# HDMI_INPUT_AD9398.net
KiCad netlist of a schematic drawn in Altium Designer
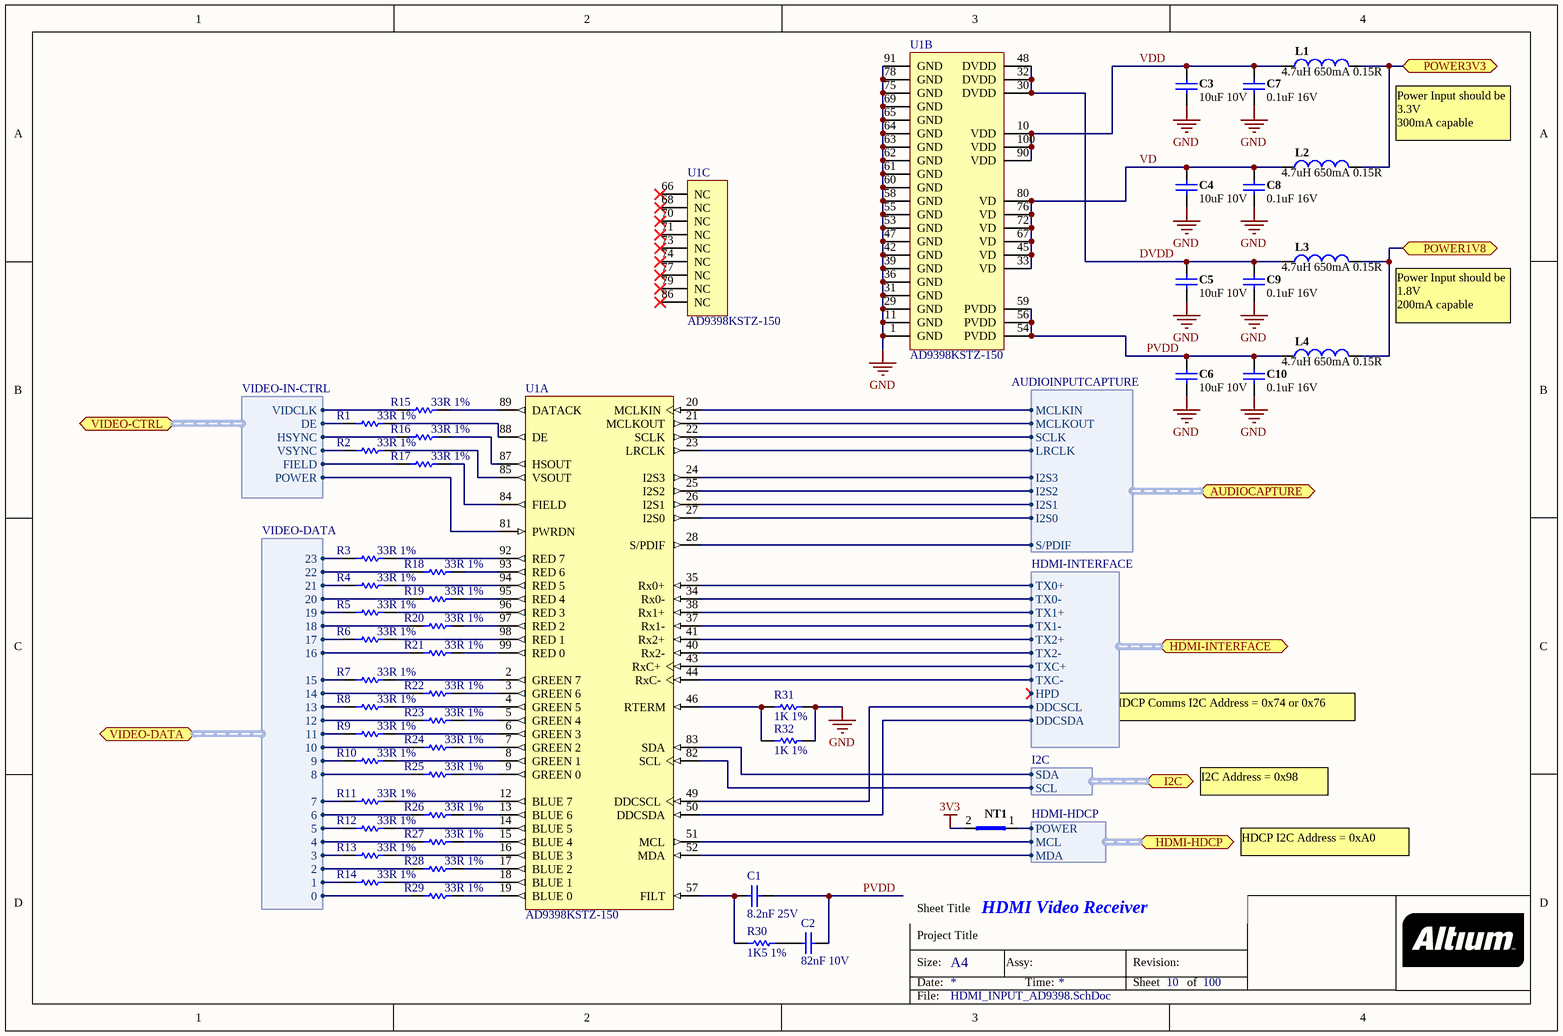
[diagram p0: HDMI_INPUT_AD9398.SchDoc]

(export (version "E")
  (design (tool "Eeschema 10.0.6"))
  (components
    (comp (ref "C1")
      (value "8.2nF 25V")
      (footprint "CAPC1005-STAR")
      (description "Capacitor, Ceramic, 8.2nF, X7R, 25V, 10%, 0402")
      (fields (field (name "TOLERANCE") "10 %"))
      (libsource (lib "AltiumDesignLibrary") (part "CAP-NP"))
    )
    (comp (ref "C2")
      (value "82nF 10V")
      (footprint "CAPC1005-STAR")
      (description "Capacitor, Ceramic, 82nF, X5R, 10V, 10%, 0402")
      (fields (field (name "TOLERANCE") "10 %"))
      (libsource (lib "AltiumDesignLibrary") (part "CAP-NP"))
    )
    (comp (ref "C3")
      (value "10uF 10V")
      (footprint "CAPC2012-STAR")
      (description "Capacitor, Ceramic, 10uF 10% 10V 0805 (2012) X5R")
      (fields (field (name "TOLERANCE") "10 %"))
      (libsource (lib "AltiumDesignLibrary") (part "CAP-NP"))
    )
    (comp (ref "C4")
      (value "10uF 10V")
      (footprint "CAPC2012-STAR")
      (description "Capacitor, Ceramic, 10uF 10% 10V 0805 (2012) X5R")
      (fields (field (name "TOLERANCE") "10 %"))
      (libsource (lib "AltiumDesignLibrary") (part "CAP-NP"))
    )
    (comp (ref "C5")
      (value "10uF 10V")
      (footprint "CAPC2012-STAR")
      (description "Capacitor, Ceramic, 10uF 10% 10V 0805 (2012) X5R")
      (fields (field (name "TOLERANCE") "10 %"))
      (libsource (lib "AltiumDesignLibrary") (part "CAP-NP"))
    )
    (comp (ref "C6")
      (value "10uF 10V")
      (footprint "CAPC2012-STAR")
      (description "Capacitor, Ceramic, 10uF 10% 10V 0805 (2012) X5R")
      (fields (field (name "TOLERANCE") "10 %"))
      (libsource (lib "AltiumDesignLibrary") (part "CAP-NP"))
    )
    (comp (ref "C7")
      (value "0.1uF 16V")
      (footprint "CAPC1005-STAR")
      (description "Capacitor, Ceramic, 0.1uF 10% 16V 0402 (1005) X7R")
      (fields (field (name "TOLERANCE") "10 %"))
      (libsource (lib "AltiumDesignLibrary") (part "CAP-NP"))
    )
    (comp (ref "C8")
      (value "0.1uF 16V")
      (footprint "CAPC1005-STAR")
      (description "Capacitor, Ceramic, 0.1uF 10% 16V 0402 (1005) X7R")
      (fields (field (name "TOLERANCE") "10 %"))
      (libsource (lib "AltiumDesignLibrary") (part "CAP-NP"))
    )
    (comp (ref "C9")
      (value "0.1uF 16V")
      (footprint "CAPC1005-STAR")
      (description "Capacitor, Ceramic, 0.1uF 10% 16V 0402 (1005) X7R")
      (fields (field (name "TOLERANCE") "10 %"))
      (libsource (lib "AltiumDesignLibrary") (part "CAP-NP"))
    )
    (comp (ref "C10")
      (value "0.1uF 16V")
      (footprint "CAPC1005-STAR")
      (description "Capacitor, Ceramic, 0.1uF 10% 16V 0402 (1005) X7R")
      (fields (field (name "TOLERANCE") "10 %"))
      (libsource (lib "AltiumDesignLibrary") (part "CAP-NP"))
    )
    (comp (ref "L1")
      (value "4.7uH 650mA 0.15R")
      (footprint "INDC3225")
      (description "Inductor, 4.7uH 650mA 0.15R 1210 (3225) LQH32CN4R7M11L")
      (libsource (lib "AltiumDesignLibrary") (part "IND"))
    )
    (comp (ref "L2")
      (value "4.7uH 650mA 0.15R")
      (footprint "INDC3225")
      (description "Inductor, 4.7uH 650mA 0.15R 1210 (3225) LQH32CN4R7M11L")
      (libsource (lib "AltiumDesignLibrary") (part "IND"))
    )
    (comp (ref "L3")
      (value "4.7uH 650mA 0.15R")
      (footprint "INDC3225")
      (description "Inductor, 4.7uH 650mA 0.15R 1210 (3225) LQH32CN4R7M11L")
      (libsource (lib "AltiumDesignLibrary") (part "IND"))
    )
    (comp (ref "L4")
      (value "4.7uH 650mA 0.15R")
      (footprint "INDC3225")
      (description "Inductor, 4.7uH 650mA 0.15R 1210 (3225) LQH32CN4R7M11L")
      (libsource (lib "AltiumDesignLibrary") (part "IND"))
    )
    (comp (ref "NT1")
      (value "Net Tie SMT2")
      (footprint "NETTIE-SMT2-31X39")
      (description "Net-Tie, Surface Mount, 2 x 2.0mm x 0.8mm SMT Pads - For 0.8mm Track")
      (libsource (lib "AltiumDesignLibrary") (part "NETTIE-SMT2"))
    )
    (comp (ref "R1")
      (value "33R 1%")
      (footprint "RESC1005-STAR")
      (description "Resistor, 33R 1% 0402 (1005)")
      (fields (field (name "TOLERANCE") "1 %"))
      (libsource (lib "AltiumDesignLibrary") (part "RES"))
    )
    (comp (ref "R2")
      (value "33R 1%")
      (footprint "RESC1005-STAR")
      (description "Resistor, 33R 1% 0402 (1005)")
      (fields (field (name "TOLERANCE") "1 %"))
      (libsource (lib "AltiumDesignLibrary") (part "RES"))
    )
    (comp (ref "R3")
      (value "33R 1%")
      (footprint "RESC1005-STAR")
      (description "Resistor, 33R 1% 0402 (1005)")
      (fields (field (name "TOLERANCE") "1 %"))
      (libsource (lib "AltiumDesignLibrary") (part "RES"))
    )
    (comp (ref "R4")
      (value "33R 1%")
      (footprint "RESC1005-STAR")
      (description "Resistor, 33R 1% 0402 (1005)")
      (fields (field (name "TOLERANCE") "1 %"))
      (libsource (lib "AltiumDesignLibrary") (part "RES"))
    )
    (comp (ref "R5")
      (value "33R 1%")
      (footprint "RESC1005-STAR")
      (description "Resistor, 33R 1% 0402 (1005)")
      (fields (field (name "TOLERANCE") "1 %"))
      (libsource (lib "AltiumDesignLibrary") (part "RES"))
    )
    (comp (ref "R6")
      (value "33R 1%")
      (footprint "RESC1005-STAR")
      (description "Resistor, 33R 1% 0402 (1005)")
      (fields (field (name "TOLERANCE") "1 %"))
      (libsource (lib "AltiumDesignLibrary") (part "RES"))
    )
    (comp (ref "R7")
      (value "33R 1%")
      (footprint "RESC1005-STAR")
      (description "Resistor, 33R 1% 0402 (1005)")
      (fields (field (name "TOLERANCE") "1 %"))
      (libsource (lib "AltiumDesignLibrary") (part "RES"))
    )
    (comp (ref "R8")
      (value "33R 1%")
      (footprint "RESC1005-STAR")
      (description "Resistor, 33R 1% 0402 (1005)")
      (fields (field (name "TOLERANCE") "1 %"))
      (libsource (lib "AltiumDesignLibrary") (part "RES"))
    )
    (comp (ref "R9")
      (value "33R 1%")
      (footprint "RESC1005-STAR")
      (description "Resistor, 33R 1% 0402 (1005)")
      (fields (field (name "TOLERANCE") "1 %"))
      (libsource (lib "AltiumDesignLibrary") (part "RES"))
    )
    (comp (ref "R10")
      (value "33R 1%")
      (footprint "RESC1005-STAR")
      (description "Resistor, 33R 1% 0402 (1005)")
      (fields (field (name "TOLERANCE") "1 %"))
      (libsource (lib "AltiumDesignLibrary") (part "RES"))
    )
    (comp (ref "R11")
      (value "33R 1%")
      (footprint "RESC1005-STAR")
      (description "Resistor, 33R 1% 0402 (1005)")
      (fields (field (name "TOLERANCE") "1 %"))
      (libsource (lib "AltiumDesignLibrary") (part "RES"))
    )
    (comp (ref "R12")
      (value "33R 1%")
      (footprint "RESC1005-STAR")
      (description "Resistor, 33R 1% 0402 (1005)")
      (fields (field (name "TOLERANCE") "1 %"))
      (libsource (lib "AltiumDesignLibrary") (part "RES"))
    )
    (comp (ref "R13")
      (value "33R 1%")
      (footprint "RESC1005-STAR")
      (description "Resistor, 33R 1% 0402 (1005)")
      (fields (field (name "TOLERANCE") "1 %"))
      (libsource (lib "AltiumDesignLibrary") (part "RES"))
    )
    (comp (ref "R14")
      (value "33R 1%")
      (footprint "RESC1005-STAR")
      (description "Resistor, 33R 1% 0402 (1005)")
      (fields (field (name "TOLERANCE") "1 %"))
      (libsource (lib "AltiumDesignLibrary") (part "RES"))
    )
    (comp (ref "R15")
      (value "33R 1%")
      (footprint "RESC1005-STAR")
      (description "Resistor, 33R 1% 0402 (1005)")
      (fields (field (name "TOLERANCE") "1 %"))
      (libsource (lib "AltiumDesignLibrary") (part "RES"))
    )
    (comp (ref "R16")
      (value "33R 1%")
      (footprint "RESC1005-STAR")
      (description "Resistor, 33R 1% 0402 (1005)")
      (fields (field (name "TOLERANCE") "1 %"))
      (libsource (lib "AltiumDesignLibrary") (part "RES"))
    )
    (comp (ref "R17")
      (value "33R 1%")
      (footprint "RESC1005-STAR")
      (description "Resistor, 33R 1% 0402 (1005)")
      (fields (field (name "TOLERANCE") "1 %"))
      (libsource (lib "AltiumDesignLibrary") (part "RES"))
    )
    (comp (ref "R18")
      (value "33R 1%")
      (footprint "RESC1005-STAR")
      (description "Resistor, 33R 1% 0402 (1005)")
      (fields (field (name "TOLERANCE") "1 %"))
      (libsource (lib "AltiumDesignLibrary") (part "RES"))
    )
    (comp (ref "R19")
      (value "33R 1%")
      (footprint "RESC1005-STAR")
      (description "Resistor, 33R 1% 0402 (1005)")
      (fields (field (name "TOLERANCE") "1 %"))
      (libsource (lib "AltiumDesignLibrary") (part "RES"))
    )
    (comp (ref "R20")
      (value "33R 1%")
      (footprint "RESC1005-STAR")
      (description "Resistor, 33R 1% 0402 (1005)")
      (fields (field (name "TOLERANCE") "1 %"))
      (libsource (lib "AltiumDesignLibrary") (part "RES"))
    )
    (comp (ref "R21")
      (value "33R 1%")
      (footprint "RESC1005-STAR")
      (description "Resistor, 33R 1% 0402 (1005)")
      (fields (field (name "TOLERANCE") "1 %"))
      (libsource (lib "AltiumDesignLibrary") (part "RES"))
    )
    (comp (ref "R22")
      (value "33R 1%")
      (footprint "RESC1005-STAR")
      (description "Resistor, 33R 1% 0402 (1005)")
      (fields (field (name "TOLERANCE") "1 %"))
      (libsource (lib "AltiumDesignLibrary") (part "RES"))
    )
    (comp (ref "R23")
      (value "33R 1%")
      (footprint "RESC1005-STAR")
      (description "Resistor, 33R 1% 0402 (1005)")
      (fields (field (name "TOLERANCE") "1 %"))
      (libsource (lib "AltiumDesignLibrary") (part "RES"))
    )
    (comp (ref "R24")
      (value "33R 1%")
      (footprint "RESC1005-STAR")
      (description "Resistor, 33R 1% 0402 (1005)")
      (fields (field (name "TOLERANCE") "1 %"))
      (libsource (lib "AltiumDesignLibrary") (part "RES"))
    )
    (comp (ref "R25")
      (value "33R 1%")
      (footprint "RESC1005-STAR")
      (description "Resistor, 33R 1% 0402 (1005)")
      (fields (field (name "TOLERANCE") "1 %"))
      (libsource (lib "AltiumDesignLibrary") (part "RES"))
    )
    (comp (ref "R26")
      (value "33R 1%")
      (footprint "RESC1005-STAR")
      (description "Resistor, 33R 1% 0402 (1005)")
      (fields (field (name "TOLERANCE") "1 %"))
      (libsource (lib "AltiumDesignLibrary") (part "RES"))
    )
    (comp (ref "R27")
      (value "33R 1%")
      (footprint "RESC1005-STAR")
      (description "Resistor, 33R 1% 0402 (1005)")
      (fields (field (name "TOLERANCE") "1 %"))
      (libsource (lib "AltiumDesignLibrary") (part "RES"))
    )
    (comp (ref "R28")
      (value "33R 1%")
      (footprint "RESC1005-STAR")
      (description "Resistor, 33R 1% 0402 (1005)")
      (fields (field (name "TOLERANCE") "1 %"))
      (libsource (lib "AltiumDesignLibrary") (part "RES"))
    )
    (comp (ref "R29")
      (value "33R 1%")
      (footprint "RESC1005-STAR")
      (description "Resistor, 33R 1% 0402 (1005)")
      (fields (field (name "TOLERANCE") "1 %"))
      (libsource (lib "AltiumDesignLibrary") (part "RES"))
    )
    (comp (ref "R30")
      (value "1K5 1%")
      (footprint "RESC1005-STAR")
      (description "Resistor, 1K5 1% 0402")
      (fields (field (name "TOLERANCE") "%"))
      (libsource (lib "AltiumDesignLibrary") (part "RES"))
    )
    (comp (ref "R31")
      (value "1K 1%")
      (footprint "RESC1005-STAR")
      (description "Resistor, 1K 1% 0402 (1005)")
      (fields (field (name "TOLERANCE") "1 %"))
      (libsource (lib "AltiumDesignLibrary") (part "RES"))
    )
    (comp (ref "R32")
      (value "1K 1%")
      (footprint "RESC1005-STAR")
      (description "Resistor, 1K 1% 0402 (1005)")
      (fields (field (name "TOLERANCE") "1 %"))
      (libsource (lib "AltiumDesignLibrary") (part "RES"))
    )
    (comp (ref "U1")
      (value "AD9398KSTZ-150")
      (footprint "ST-100-1_V")
      (description "AD9398KSTZ-150, HDMI Video Receiver, TQFP100")
      (libsource (lib "AltiumDesignLibrary") (part "AD9398KSTZ-150"))
    )
  )
  (nets
    (net (code "7") (name "/0") (class "Default")
      (node (ref "R29") (pin "1") (pinfunction "1_1") (pintype "passive"))
    )
    (net (code "8") (name "/1") (class "Default")
      (node (ref "R14") (pin "1") (pinfunction "1_1") (pintype "passive"))
    )
    (net (code "9") (name "/2") (class "Default")
      (node (ref "R28") (pin "1") (pinfunction "1_1") (pintype "passive"))
    )
    (net (code "10") (name "/3") (class "Default")
      (node (ref "R13") (pin "1") (pinfunction "1_1") (pintype "passive"))
    )
    (net (code "11") (name "/4") (class "Default")
      (node (ref "R27") (pin "1") (pinfunction "1_1") (pintype "passive"))
    )
    (net (code "12") (name "/5") (class "Default")
      (node (ref "R12") (pin "1") (pinfunction "1_1") (pintype "passive"))
    )
    (net (code "13") (name "/6") (class "Default")
      (node (ref "R26") (pin "1") (pinfunction "1_1") (pintype "passive"))
    )
    (net (code "14") (name "/7") (class "Default")
      (node (ref "R11") (pin "1") (pinfunction "1_1") (pintype "passive"))
    )
    (net (code "15") (name "/8") (class "Default")
      (node (ref "R25") (pin "1") (pinfunction "1_1") (pintype "passive"))
    )
    (net (code "16") (name "/9") (class "Default")
      (node (ref "R10") (pin "1") (pinfunction "1_1") (pintype "passive"))
    )
    (net (code "17") (name "/10") (class "Default")
      (node (ref "R24") (pin "1") (pinfunction "1_1") (pintype "passive"))
    )
    (net (code "18") (name "/11") (class "Default")
      (node (ref "R9") (pin "1") (pinfunction "1_1") (pintype "passive"))
    )
    (net (code "19") (name "/12") (class "Default")
      (node (ref "R23") (pin "1") (pinfunction "1_1") (pintype "passive"))
    )
    (net (code "20") (name "/13") (class "Default")
      (node (ref "R8") (pin "1") (pinfunction "1_1") (pintype "passive"))
    )
    (net (code "21") (name "/14") (class "Default")
      (node (ref "R22") (pin "1") (pinfunction "1_1") (pintype "passive"))
    )
    (net (code "22") (name "/15") (class "Default")
      (node (ref "R7") (pin "1") (pinfunction "1_1") (pintype "passive"))
    )
    (net (code "23") (name "/16") (class "Default")
      (node (ref "R21") (pin "1") (pinfunction "1_1") (pintype "passive"))
    )
    (net (code "24") (name "/17") (class "Default")
      (node (ref "R6") (pin "1") (pinfunction "1_1") (pintype "passive"))
    )
    (net (code "25") (name "/18") (class "Default")
      (node (ref "R20") (pin "1") (pinfunction "1_1") (pintype "passive"))
    )
    (net (code "26") (name "/19") (class "Default")
      (node (ref "R5") (pin "1") (pinfunction "1_1") (pintype "passive"))
    )
    (net (code "27") (name "/20") (class "Default")
      (node (ref "R19") (pin "1") (pinfunction "1_1") (pintype "passive"))
    )
    (net (code "28") (name "/21") (class "Default")
      (node (ref "R4") (pin "1") (pinfunction "1_1") (pintype "passive"))
    )
    (net (code "29") (name "/22") (class "Default")
      (node (ref "R18") (pin "1") (pinfunction "1_1") (pintype "passive"))
    )
    (net (code "30") (name "/23") (class "Default")
      (node (ref "R3") (pin "1") (pinfunction "1_1") (pintype "passive"))
    )
    (net (code "31") (name "/DDCSCL") (class "Default")
      (node (ref "U1") (pin "49") (pinfunction "DDCSCL_49") (pintype "input"))
    )
    (net (code "32") (name "/DDCSDA") (class "Default")
      (node (ref "U1") (pin "50") (pinfunction "DDCSDA_50") (pintype "input"))
    )
    (net (code "33") (name "/DE") (class "Default")
      (node (ref "R1") (pin "1") (pinfunction "1_1") (pintype "passive"))
    )
    (net (code "34") (name "/DVDD") (class "Default")
      (node (ref "C5") (pin "1") (pinfunction "1_1") (pintype "passive"))
      (node (ref "C9") (pin "1") (pinfunction "1_1") (pintype "passive"))
      (node (ref "L3") (pin "2") (pinfunction "2_2") (pintype "passive"))
      (node (ref "U1") (pin "30") (pinfunction "DVDD_30") (pintype "power_in"))
      (node (ref "U1") (pin "32") (pinfunction "DVDD_32") (pintype "power_in"))
      (node (ref "U1") (pin "48") (pinfunction "DVDD_48") (pintype "power_in"))
    )
    (net (code "35") (name "/FIELD") (class "Default")
      (node (ref "R17") (pin "1") (pinfunction "1_1") (pintype "passive"))
    )
    (net (code "36") (name "/HSYNC") (class "Default")
      (node (ref "R16") (pin "1") (pinfunction "1_1") (pintype "passive"))
    )
    (net (code "37") (name "/I2S0") (class "Default")
      (node (ref "U1") (pin "27") (pinfunction "I2S0_27") (pintype "output"))
    )
    (net (code "38") (name "/I2S1") (class "Default")
      (node (ref "U1") (pin "26") (pinfunction "I2S1_26") (pintype "output"))
    )
    (net (code "39") (name "/I2S2") (class "Default")
      (node (ref "U1") (pin "25") (pinfunction "I2S2_25") (pintype "output"))
    )
    (net (code "40") (name "/I2S3") (class "Default")
      (node (ref "U1") (pin "24") (pinfunction "I2S3_24") (pintype "output"))
    )
    (net (code "41") (name "/LRCLK") (class "Default")
      (node (ref "U1") (pin "23") (pinfunction "LRCLK_23") (pintype "output"))
    )
    (net (code "42") (name "/MCL") (class "Default")
      (node (ref "U1") (pin "51") (pinfunction "MCL_51") (pintype "output"))
    )
    (net (code "43") (name "/MCLKIN") (class "Default")
      (node (ref "U1") (pin "20") (pinfunction "MCLKIN_20") (pintype "input"))
    )
    (net (code "44") (name "/MCLKOUT") (class "Default")
      (node (ref "U1") (pin "21") (pinfunction "MCLKOUT_21") (pintype "output"))
    )
    (net (code "45") (name "/MDA") (class "Default")
      (node (ref "U1") (pin "52") (pinfunction "MDA_52") (pintype "input"))
    )
    (net (code "46") (name "/POWER1V8") (class "Default")
      (node (ref "L3") (pin "1") (pinfunction "1_1") (pintype "passive"))
      (node (ref "L4") (pin "1") (pinfunction "1_1") (pintype "passive"))
    )
    (net (code "47") (name "/POWER3V3") (class "Default")
      (node (ref "L1") (pin "1") (pinfunction "1_1") (pintype "passive"))
      (node (ref "L2") (pin "1") (pinfunction "1_1") (pintype "passive"))
    )
    (net (code "48") (name "/PVDD") (class "Default")
      (node (ref "C1") (pin "2") (pinfunction "2_2") (pintype "passive"))
      (node (ref "C10") (pin "1") (pinfunction "1_1") (pintype "passive"))
      (node (ref "C2") (pin "2") (pinfunction "2_2") (pintype "passive"))
      (node (ref "C6") (pin "1") (pinfunction "1_1") (pintype "passive"))
      (node (ref "L4") (pin "2") (pinfunction "2_2") (pintype "passive"))
      (node (ref "U1") (pin "54") (pinfunction "PVDD_54") (pintype "power_in"))
      (node (ref "U1") (pin "56") (pinfunction "PVDD_56") (pintype "power_in"))
      (node (ref "U1") (pin "59") (pinfunction "PVDD_59") (pintype "power_in"))
    )
    (net (code "49") (name "/SCL") (class "Default")
      (node (ref "U1") (pin "82") (pinfunction "SCL_82") (pintype "input"))
    )
    (net (code "50") (name "/SCLK") (class "Default")
      (node (ref "U1") (pin "22") (pinfunction "SCLK_22") (pintype "output"))
    )
    (net (code "51") (name "/SDA") (class "Default")
      (node (ref "U1") (pin "83") (pinfunction "SDA_83") (pintype "input"))
    )
    (net (code "52") (name "/S{slash}PDIF") (class "Default")
      (node (ref "U1") (pin "28") (pinfunction "S/PDIF_28") (pintype "output"))
    )
    (net (code "53") (name "/TX0+") (class "Default")
      (node (ref "U1") (pin "35") (pinfunction "Rx0+_35") (pintype "input"))
    )
    (net (code "54") (name "/TX0-") (class "Default")
      (node (ref "U1") (pin "34") (pinfunction "Rx0-_34") (pintype "input"))
    )
    (net (code "55") (name "/TX1+") (class "Default")
      (node (ref "U1") (pin "38") (pinfunction "Rx1+_38") (pintype "input"))
    )
    (net (code "56") (name "/TX1-") (class "Default")
      (node (ref "U1") (pin "37") (pinfunction "Rx1-_37") (pintype "input"))
    )
    (net (code "57") (name "/TX2+") (class "Default")
      (node (ref "U1") (pin "41") (pinfunction "Rx2+_41") (pintype "input"))
    )
    (net (code "58") (name "/TX2-") (class "Default")
      (node (ref "U1") (pin "40") (pinfunction "Rx2-_40") (pintype "input"))
    )
    (net (code "59") (name "/TXC+") (class "Default")
      (node (ref "U1") (pin "43") (pinfunction "RxC+_43") (pintype "input"))
    )
    (net (code "60") (name "/TXC-") (class "Default")
      (node (ref "U1") (pin "44") (pinfunction "RxC-_44") (pintype "input"))
    )
    (net (code "61") (name "/VD") (class "Default")
      (node (ref "C4") (pin "1") (pinfunction "1_1") (pintype "passive"))
      (node (ref "C8") (pin "1") (pinfunction "1_1") (pintype "passive"))
      (node (ref "L2") (pin "2") (pinfunction "2_2") (pintype "passive"))
      (node (ref "U1") (pin "33") (pinfunction "VD_33") (pintype "power_in"))
      (node (ref "U1") (pin "45") (pinfunction "VD_45") (pintype "power_in"))
      (node (ref "U1") (pin "67") (pinfunction "VD_67") (pintype "power_in"))
      (node (ref "U1") (pin "72") (pinfunction "VD_72") (pintype "power_in"))
      (node (ref "U1") (pin "76") (pinfunction "VD_76") (pintype "power_in"))
      (node (ref "U1") (pin "80") (pinfunction "VD_80") (pintype "power_in"))
    )
    (net (code "62") (name "/VDD") (class "Default")
      (node (ref "C3") (pin "1") (pinfunction "1_1") (pintype "passive"))
      (node (ref "C7") (pin "1") (pinfunction "1_1") (pintype "passive"))
      (node (ref "L1") (pin "2") (pinfunction "2_2") (pintype "passive"))
      (node (ref "U1") (pin "10") (pinfunction "VDD_10") (pintype "power_in"))
      (node (ref "U1") (pin "100") (pinfunction "VDD_100") (pintype "power_in"))
      (node (ref "U1") (pin "90") (pinfunction "VDD_90") (pintype "power_in"))
    )
    (net (code "63") (name "/VIDCLK") (class "Default")
      (node (ref "R15") (pin "1") (pinfunction "1_1") (pintype "passive"))
    )
    (net (code "64") (name "/VSYNC") (class "Default")
      (node (ref "R2") (pin "1") (pinfunction "1_1") (pintype "passive"))
    )
    (net (code "71") (name "3V3") (class "Default")
      (node (ref "NT1") (pin "2") (pinfunction "Net2_2") (pintype "passive"))
    )
    (net (code "72") (name "GND") (class "Default")
      (node (ref "C10") (pin "2") (pinfunction "2_2") (pintype "passive"))
      (node (ref "C3") (pin "2") (pinfunction "2_2") (pintype "passive"))
      (node (ref "C4") (pin "2") (pinfunction "2_2") (pintype "passive"))
      (node (ref "C5") (pin "2") (pinfunction "2_2") (pintype "passive"))
      (node (ref "C6") (pin "2") (pinfunction "2_2") (pintype "passive"))
      (node (ref "C7") (pin "2") (pinfunction "2_2") (pintype "passive"))
      (node (ref "C8") (pin "2") (pinfunction "2_2") (pintype "passive"))
      (node (ref "C9") (pin "2") (pinfunction "2_2") (pintype "passive"))
      (node (ref "R31") (pin "2") (pinfunction "2_2") (pintype "passive"))
      (node (ref "R32") (pin "2") (pinfunction "2_2") (pintype "passive"))
      (node (ref "U1") (pin "1") (pinfunction "GND_1") (pintype "power_in"))
      (node (ref "U1") (pin "11") (pinfunction "GND_11") (pintype "power_in"))
      (node (ref "U1") (pin "29") (pinfunction "GND_29") (pintype "power_in"))
      (node (ref "U1") (pin "31") (pinfunction "GND_31") (pintype "power_in"))
      (node (ref "U1") (pin "36") (pinfunction "GND_36") (pintype "power_in"))
      (node (ref "U1") (pin "39") (pinfunction "GND_39") (pintype "power_in"))
      (node (ref "U1") (pin "42") (pinfunction "GND_42") (pintype "power_in"))
      (node (ref "U1") (pin "47") (pinfunction "GND_47") (pintype "power_in"))
      (node (ref "U1") (pin "53") (pinfunction "GND_53") (pintype "power_in"))
      (node (ref "U1") (pin "55") (pinfunction "GND_55") (pintype "power_in"))
      (node (ref "U1") (pin "58") (pinfunction "GND_58") (pintype "power_in"))
      (node (ref "U1") (pin "60") (pinfunction "GND_60") (pintype "power_in"))
      (node (ref "U1") (pin "61") (pinfunction "GND_61") (pintype "power_in"))
      (node (ref "U1") (pin "62") (pinfunction "GND_62") (pintype "power_in"))
      (node (ref "U1") (pin "63") (pinfunction "GND_63") (pintype "power_in"))
      (node (ref "U1") (pin "64") (pinfunction "GND_64") (pintype "power_in"))
      (node (ref "U1") (pin "65") (pinfunction "GND_65") (pintype "power_in"))
      (node (ref "U1") (pin "69") (pinfunction "GND_69") (pintype "power_in"))
      (node (ref "U1") (pin "75") (pinfunction "GND_75") (pintype "power_in"))
      (node (ref "U1") (pin "78") (pinfunction "GND_78") (pintype "power_in"))
      (node (ref "U1") (pin "91") (pinfunction "GND_91") (pintype "power_in"))
    )
    (net (code "73") (name "Net-(C2-Pad1)") (class "Default")
      (node (ref "C2") (pin "1") (pinfunction "1_1") (pintype "passive"))
      (node (ref "R30") (pin "2") (pinfunction "2_2") (pintype "passive"))
    )
    (net (code "74") (name "Net-(U1A-BLUE_0)") (class "Default")
      (node (ref "R29") (pin "2") (pinfunction "2_2") (pintype "passive"))
      (node (ref "U1") (pin "19") (pinfunction "BLUE_0_19") (pintype "output"))
    )
    (net (code "75") (name "Net-(U1A-BLUE_1)") (class "Default")
      (node (ref "R14") (pin "2") (pinfunction "2_2") (pintype "passive"))
      (node (ref "U1") (pin "18") (pinfunction "BLUE_1_18") (pintype "output"))
    )
    (net (code "76") (name "Net-(U1A-BLUE_2)") (class "Default")
      (node (ref "R28") (pin "2") (pinfunction "2_2") (pintype "passive"))
      (node (ref "U1") (pin "17") (pinfunction "BLUE_2_17") (pintype "output"))
    )
    (net (code "77") (name "Net-(U1A-BLUE_3)") (class "Default")
      (node (ref "R13") (pin "2") (pinfunction "2_2") (pintype "passive"))
      (node (ref "U1") (pin "16") (pinfunction "BLUE_3_16") (pintype "output"))
    )
    (net (code "78") (name "Net-(U1A-BLUE_4)") (class "Default")
      (node (ref "R27") (pin "2") (pinfunction "2_2") (pintype "passive"))
      (node (ref "U1") (pin "15") (pinfunction "BLUE_4_15") (pintype "output"))
    )
    (net (code "79") (name "Net-(U1A-BLUE_5)") (class "Default")
      (node (ref "R12") (pin "2") (pinfunction "2_2") (pintype "passive"))
      (node (ref "U1") (pin "14") (pinfunction "BLUE_5_14") (pintype "output"))
    )
    (net (code "80") (name "Net-(U1A-BLUE_6)") (class "Default")
      (node (ref "R26") (pin "2") (pinfunction "2_2") (pintype "passive"))
      (node (ref "U1") (pin "13") (pinfunction "BLUE_6_13") (pintype "output"))
    )
    (net (code "81") (name "Net-(U1A-BLUE_7)") (class "Default")
      (node (ref "R11") (pin "2") (pinfunction "2_2") (pintype "passive"))
      (node (ref "U1") (pin "12") (pinfunction "BLUE_7_12") (pintype "output"))
    )
    (net (code "82") (name "Net-(U1A-DATACK)") (class "Default")
      (node (ref "R15") (pin "2") (pinfunction "2_2") (pintype "passive"))
      (node (ref "U1") (pin "89") (pinfunction "DATACK_89") (pintype "output"))
    )
    (net (code "83") (name "Net-(U1A-DE)") (class "Default")
      (node (ref "R1") (pin "2") (pinfunction "2_2") (pintype "passive"))
      (node (ref "U1") (pin "88") (pinfunction "DE_88") (pintype "output"))
    )
    (net (code "84") (name "Net-(U1A-FIELD)") (class "Default")
      (node (ref "R17") (pin "2") (pinfunction "2_2") (pintype "passive"))
      (node (ref "U1") (pin "84") (pinfunction "FIELD_84") (pintype "output"))
    )
    (net (code "85") (name "Net-(U1A-FILT)") (class "Default")
      (node (ref "C1") (pin "1") (pinfunction "1_1") (pintype "passive"))
      (node (ref "R30") (pin "1") (pinfunction "1_1") (pintype "passive"))
      (node (ref "U1") (pin "57") (pinfunction "FILT_57") (pintype "input"))
    )
    (net (code "86") (name "Net-(U1A-GREEN_0)") (class "Default")
      (node (ref "R25") (pin "2") (pinfunction "2_2") (pintype "passive"))
      (node (ref "U1") (pin "9") (pinfunction "GREEN_0_9") (pintype "output"))
    )
    (net (code "87") (name "Net-(U1A-GREEN_1)") (class "Default")
      (node (ref "R10") (pin "2") (pinfunction "2_2") (pintype "passive"))
      (node (ref "U1") (pin "8") (pinfunction "GREEN_1_8") (pintype "output"))
    )
    (net (code "88") (name "Net-(U1A-GREEN_2)") (class "Default")
      (node (ref "R24") (pin "2") (pinfunction "2_2") (pintype "passive"))
      (node (ref "U1") (pin "7") (pinfunction "GREEN_2_7") (pintype "output"))
    )
    (net (code "89") (name "Net-(U1A-GREEN_3)") (class "Default")
      (node (ref "R9") (pin "2") (pinfunction "2_2") (pintype "passive"))
      (node (ref "U1") (pin "6") (pinfunction "GREEN_3_6") (pintype "output"))
    )
    (net (code "90") (name "Net-(U1A-GREEN_4)") (class "Default")
      (node (ref "R23") (pin "2") (pinfunction "2_2") (pintype "passive"))
      (node (ref "U1") (pin "5") (pinfunction "GREEN_4_5") (pintype "output"))
    )
    (net (code "91") (name "Net-(U1A-GREEN_5)") (class "Default")
      (node (ref "R8") (pin "2") (pinfunction "2_2") (pintype "passive"))
      (node (ref "U1") (pin "4") (pinfunction "GREEN_5_4") (pintype "output"))
    )
    (net (code "92") (name "Net-(U1A-GREEN_6)") (class "Default")
      (node (ref "R22") (pin "2") (pinfunction "2_2") (pintype "passive"))
      (node (ref "U1") (pin "3") (pinfunction "GREEN_6_3") (pintype "output"))
    )
    (net (code "93") (name "Net-(U1A-GREEN_7)") (class "Default")
      (node (ref "R7") (pin "2") (pinfunction "2_2") (pintype "passive"))
      (node (ref "U1") (pin "2") (pinfunction "GREEN_7_2") (pintype "output"))
    )
    (net (code "94") (name "Net-(U1A-HSOUT)") (class "Default")
      (node (ref "R16") (pin "2") (pinfunction "2_2") (pintype "passive"))
      (node (ref "U1") (pin "87") (pinfunction "HSOUT_87") (pintype "output"))
    )
    (net (code "95") (name "Net-(U1A-RED_0)") (class "Default")
      (node (ref "R21") (pin "2") (pinfunction "2_2") (pintype "passive"))
      (node (ref "U1") (pin "99") (pinfunction "RED_0_99") (pintype "output"))
    )
    (net (code "96") (name "Net-(U1A-RED_1)") (class "Default")
      (node (ref "R6") (pin "2") (pinfunction "2_2") (pintype "passive"))
      (node (ref "U1") (pin "98") (pinfunction "RED_1_98") (pintype "output"))
    )
    (net (code "97") (name "Net-(U1A-RED_2)") (class "Default")
      (node (ref "R20") (pin "2") (pinfunction "2_2") (pintype "passive"))
      (node (ref "U1") (pin "97") (pinfunction "RED_2_97") (pintype "output"))
    )
    (net (code "98") (name "Net-(U1A-RED_3)") (class "Default")
      (node (ref "R5") (pin "2") (pinfunction "2_2") (pintype "passive"))
      (node (ref "U1") (pin "96") (pinfunction "RED_3_96") (pintype "output"))
    )
    (net (code "99") (name "Net-(U1A-RED_4)") (class "Default")
      (node (ref "R19") (pin "2") (pinfunction "2_2") (pintype "passive"))
      (node (ref "U1") (pin "95") (pinfunction "RED_4_95") (pintype "output"))
    )
    (net (code "100") (name "Net-(U1A-RED_5)") (class "Default")
      (node (ref "R4") (pin "2") (pinfunction "2_2") (pintype "passive"))
      (node (ref "U1") (pin "94") (pinfunction "RED_5_94") (pintype "output"))
    )
    (net (code "101") (name "Net-(U1A-RED_6)") (class "Default")
      (node (ref "R18") (pin "2") (pinfunction "2_2") (pintype "passive"))
      (node (ref "U1") (pin "93") (pinfunction "RED_6_93") (pintype "output"))
    )
    (net (code "102") (name "Net-(U1A-RED_7)") (class "Default")
      (node (ref "R3") (pin "2") (pinfunction "2_2") (pintype "passive"))
      (node (ref "U1") (pin "92") (pinfunction "RED_7_92") (pintype "output"))
    )
    (net (code "103") (name "Net-(U1A-RTERM)") (class "Default")
      (node (ref "R31") (pin "1") (pinfunction "1_1") (pintype "passive"))
      (node (ref "R32") (pin "1") (pinfunction "1_1") (pintype "passive"))
      (node (ref "U1") (pin "46") (pinfunction "RTERM_46") (pintype "input"))
    )
    (net (code "104") (name "Net-(U1A-VSOUT)") (class "Default")
      (node (ref "R2") (pin "2") (pinfunction "2_2") (pintype "passive"))
      (node (ref "U1") (pin "85") (pinfunction "VSOUT_85") (pintype "output"))
    )
    (net (code "105") (name "unconnected-(NT1-Net1-Pad1)") (class "Default")
      (node (ref "NT1") (pin "1") (pinfunction "Net1_1") (pintype "passive"))
    )
    (net (code "106") (name "unconnected-(U1A-PWRDN-Pad81)") (class "Default")
      (node (ref "U1") (pin "81") (pinfunction "PWRDN_81") (pintype "input"))
    )
    (net (code "107") (name "unconnected-(U1C-NC-Pad66)") (class "Default")
      (node (ref "U1") (pin "66") (pinfunction "NC_66") (pintype "passive+no_connect"))
    )
    (net (code "108") (name "unconnected-(U1C-NC-Pad68)") (class "Default")
      (node (ref "U1") (pin "68") (pinfunction "NC_68") (pintype "passive+no_connect"))
    )
    (net (code "109") (name "unconnected-(U1C-NC-Pad70)") (class "Default")
      (node (ref "U1") (pin "70") (pinfunction "NC_70") (pintype "passive+no_connect"))
    )
    (net (code "110") (name "unconnected-(U1C-NC-Pad71)") (class "Default")
      (node (ref "U1") (pin "71") (pinfunction "NC_71") (pintype "passive+no_connect"))
    )
    (net (code "111") (name "unconnected-(U1C-NC-Pad73)") (class "Default")
      (node (ref "U1") (pin "73") (pinfunction "NC_73") (pintype "passive+no_connect"))
    )
    (net (code "112") (name "unconnected-(U1C-NC-Pad74)") (class "Default")
      (node (ref "U1") (pin "74") (pinfunction "NC_74") (pintype "passive+no_connect"))
    )
    (net (code "113") (name "unconnected-(U1C-NC-Pad77)") (class "Default")
      (node (ref "U1") (pin "77") (pinfunction "NC_77") (pintype "passive+no_connect"))
    )
    (net (code "114") (name "unconnected-(U1C-NC-Pad79)") (class "Default")
      (node (ref "U1") (pin "79") (pinfunction "NC_79") (pintype "passive+no_connect"))
    )
    (net (code "115") (name "unconnected-(U1C-NC-Pad86)") (class "Default")
      (node (ref "U1") (pin "86") (pinfunction "NC_86") (pintype "passive+no_connect"))
    )
  )
)
